# ArduinoSmarticleNoAccel.net
KiCad netlist of a schematic drawn in EAGLE
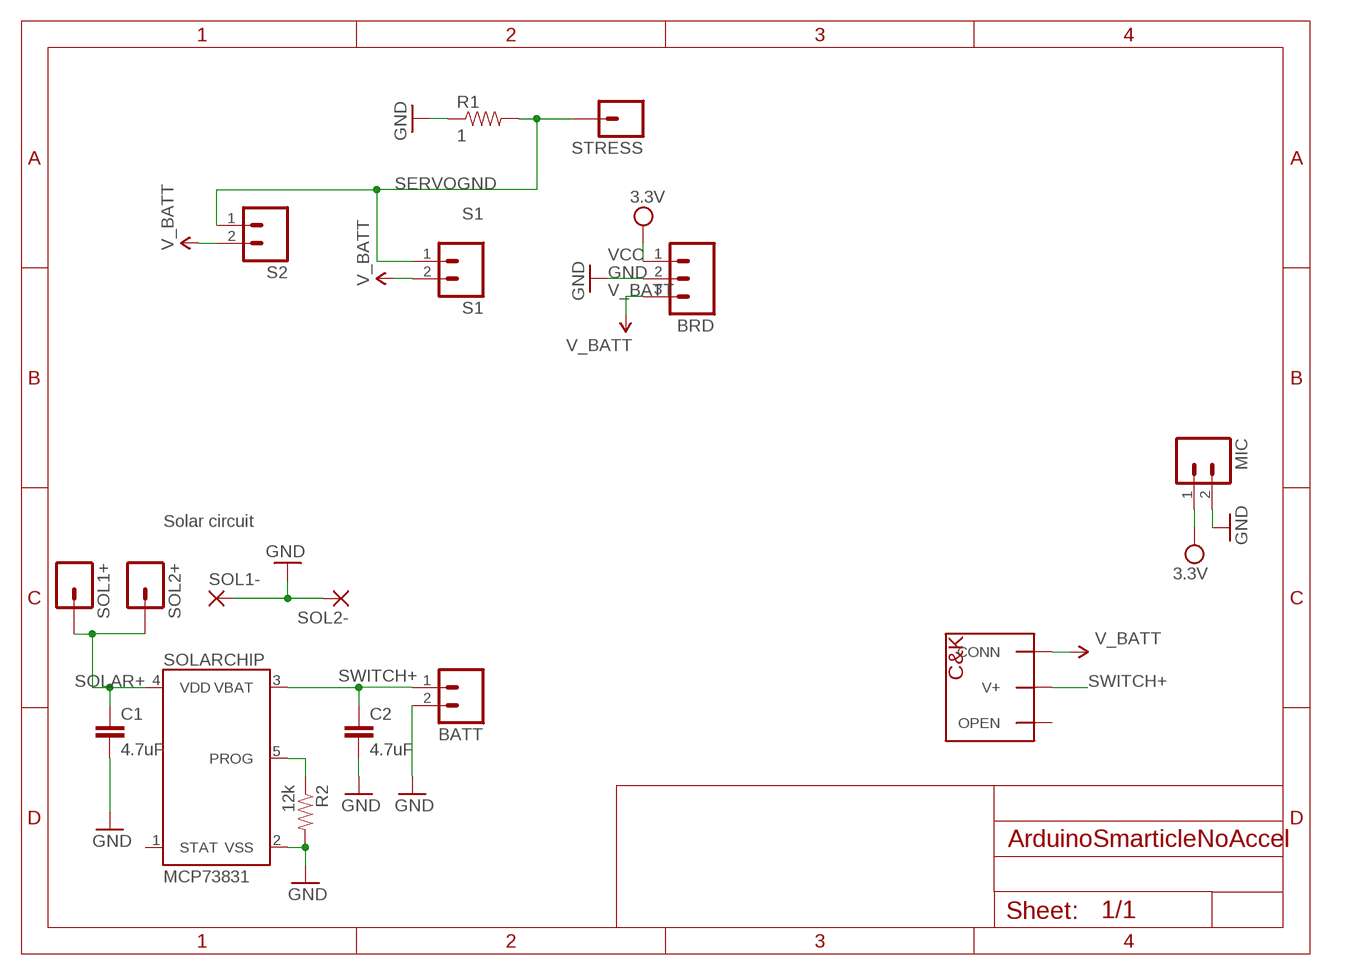
[diagram p0: schematic, sheet 1]

(export (version "E")
  (design (tool "Eeschema 10.0.6"))
  (components
    (comp (ref "BATT")
      (value "M02PTH")
      (footprint "eagle-import:1X02")
      (libsource (lib "eagle-import") (part "M02PTH"))
    )
    (comp (ref "BRD")
      (value "M03PTH")
      (footprint "eagle-import:1X03")
      (libsource (lib "eagle-import") (part "M03PTH"))
    )
    (comp (ref "C1")
      (value "4.7uF")
      (footprint "eagle-import:0603-CAP")
      (libsource (lib "eagle-import") (part "4.7UF-6.3V-10%(0603)0603"))
    )
    (comp (ref "C2")
      (value "4.7uF")
      (footprint "eagle-import:0603-CAP")
      (libsource (lib "eagle-import") (part "4.7UF-6.3V-10%(0603)0603"))
    )
    (comp (ref "MIC")
      (value "M02PTH")
      (footprint "eagle-import:1X02")
      (libsource (lib "eagle-import") (part "M02PTH"))
    )
    (comp (ref "R1")
      (value "1")
      (footprint "eagle-import:0603-RES")
      (libsource (lib "eagle-import") (part "2.0KOHM1/10W5%(0603)"))
    )
    (comp (ref "R2")
      (value "12k")
      (footprint "eagle-import:0603")
      (libsource (lib "eagle-import") (part "10.5KOHM1/10W1%(0603)"))
    )
    (comp (ref "S1")
      (value "S1")
      (footprint "eagle-import:1X02")
      (libsource (lib "eagle-import") (part "M02PTH"))
    )
    (comp (ref "S2")
      (value "M02PTH")
      (footprint "eagle-import:1X02")
      (libsource (lib "eagle-import") (part "M02PTH"))
    )
    (comp (ref "SOL1+")
      (value "M01PTH")
      (footprint "eagle-import:1X01")
      (libsource (lib "eagle-import") (part "M01PTH"))
    )
    (comp (ref "SOL1-")
      (value "1,6/0,9")
      (footprint "eagle-import:1,6_0,9")
      (libsource (lib "eagle-import") (part "1,6/0,9"))
    )
    (comp (ref "SOL2+")
      (value "M01PTH")
      (footprint "eagle-import:1X01")
      (libsource (lib "eagle-import") (part "M01PTH"))
    )
    (comp (ref "SOL2-")
      (value "1,6/0,9")
      (footprint "eagle-import:1,6_0,9")
      (libsource (lib "eagle-import") (part "1,6/0,9"))
    )
    (comp (ref "SOLARCHIP")
      (value "MCP73831")
      (footprint "eagle-import:SOT23-5")
      (libsource (lib "eagle-import") (part "MCP73831"))
    )
    (comp (ref "STRESS")
      (value "M01PTH")
      (footprint "eagle-import:1X01")
      (libsource (lib "eagle-import") (part "M01PTH"))
    )
    (comp (ref "U$1")
      (value "WILL-BLACKSLIDESWITCH")
      (footprint "eagle-import:WILL-BLACKSLIDESWITCH")
      (libsource (lib "eagle-import") (part "WILL-BLACKSLIDESWITCH"))
    )
  )
  (nets
    (net (code "1") (name "/SERVOGND") (class "Default")
      (node (ref "R1") (pin "2") (pinfunction "2_2") (pintype "passive"))
      (node (ref "S1") (pin "1") (pinfunction "1_1") (pintype "passive"))
      (node (ref "S2") (pin "1") (pinfunction "1_1") (pintype "passive"))
      (node (ref "STRESS") (pin "1") (pinfunction "1_1") (pintype "passive"))
    )
    (net (code "2") (name "/SOLAR+") (class "Default")
      (node (ref "C1") (pin "1") (pinfunction "1_1") (pintype "passive"))
      (node (ref "SOL1+") (pin "1") (pinfunction "1_1") (pintype "passive"))
      (node (ref "SOL2+") (pin "1") (pinfunction "1_1") (pintype "passive"))
      (node (ref "SOLARCHIP") (pin "4") (pinfunction "VDD_4") (pintype "power_in"))
    )
    (net (code "3") (name "/SWITCH+") (class "Default")
      (node (ref "BATT") (pin "1") (pinfunction "1_1") (pintype "passive"))
      (node (ref "C2") (pin "1") (pinfunction "1_1") (pintype "passive"))
      (node (ref "SOLARCHIP") (pin "3") (pinfunction "VBAT_3") (pintype "power_in"))
      (node (ref "U$1") (pin "V+") (pinfunction "V+_V+") (pintype "bidirectional"))
    )
    (net (code "4") (name "3.3V") (class "Default")
      (node (ref "BRD") (pin "1") (pinfunction "1_1") (pintype "passive"))
      (node (ref "MIC") (pin "1") (pinfunction "1_1") (pintype "passive"))
    )
    (net (code "5") (name "GND") (class "Default")
      (node (ref "BATT") (pin "2") (pinfunction "2_2") (pintype "passive"))
      (node (ref "BRD") (pin "2") (pinfunction "2_2") (pintype "passive"))
      (node (ref "C1") (pin "2") (pinfunction "2_2") (pintype "passive"))
      (node (ref "C2") (pin "2") (pinfunction "2_2") (pintype "passive"))
      (node (ref "MIC") (pin "2") (pinfunction "2_2") (pintype "passive"))
      (node (ref "R1") (pin "1") (pinfunction "1_1") (pintype "passive"))
      (node (ref "R2") (pin "2") (pinfunction "2_2") (pintype "passive"))
      (node (ref "SOL1-") (pin "1") (pinfunction "P_1") (pintype "passive"))
      (node (ref "SOL2-") (pin "1") (pinfunction "P_1") (pintype "passive"))
      (node (ref "SOLARCHIP") (pin "2") (pinfunction "VSS_2") (pintype "power_in"))
    )
    (net (code "6") (name "Net-(SOLARCHIP-PROG)") (class "Default")
      (node (ref "R2") (pin "1") (pinfunction "1_1") (pintype "passive"))
      (node (ref "SOLARCHIP") (pin "5") (pinfunction "PROG_5") (pintype "input"))
    )
    (net (code "7") (name "V_BATT") (class "Default")
      (node (ref "BRD") (pin "3") (pinfunction "3_3") (pintype "passive"))
      (node (ref "S1") (pin "2") (pinfunction "2_2") (pintype "passive"))
      (node (ref "S2") (pin "2") (pinfunction "2_2") (pintype "passive"))
      (node (ref "U$1") (pin "CONN") (pinfunction "CONN_CONN") (pintype "bidirectional"))
    )
    (net (code "8") (name "unconnected-(SOLARCHIP-STAT-Pad1)") (class "Default")
      (node (ref "SOLARCHIP") (pin "1") (pinfunction "STAT_1") (pintype "output"))
    )
    (net (code "9") (name "unconnected-(U$1-OPEN-PadNC)") (class "Default")
      (node (ref "U$1") (pin "NC") (pinfunction "OPEN_NC") (pintype "bidirectional"))
    )
  )
)
